# 17_-ETH_CONNECTOR.net
KiCad netlist of a schematic drawn in Altium Designer
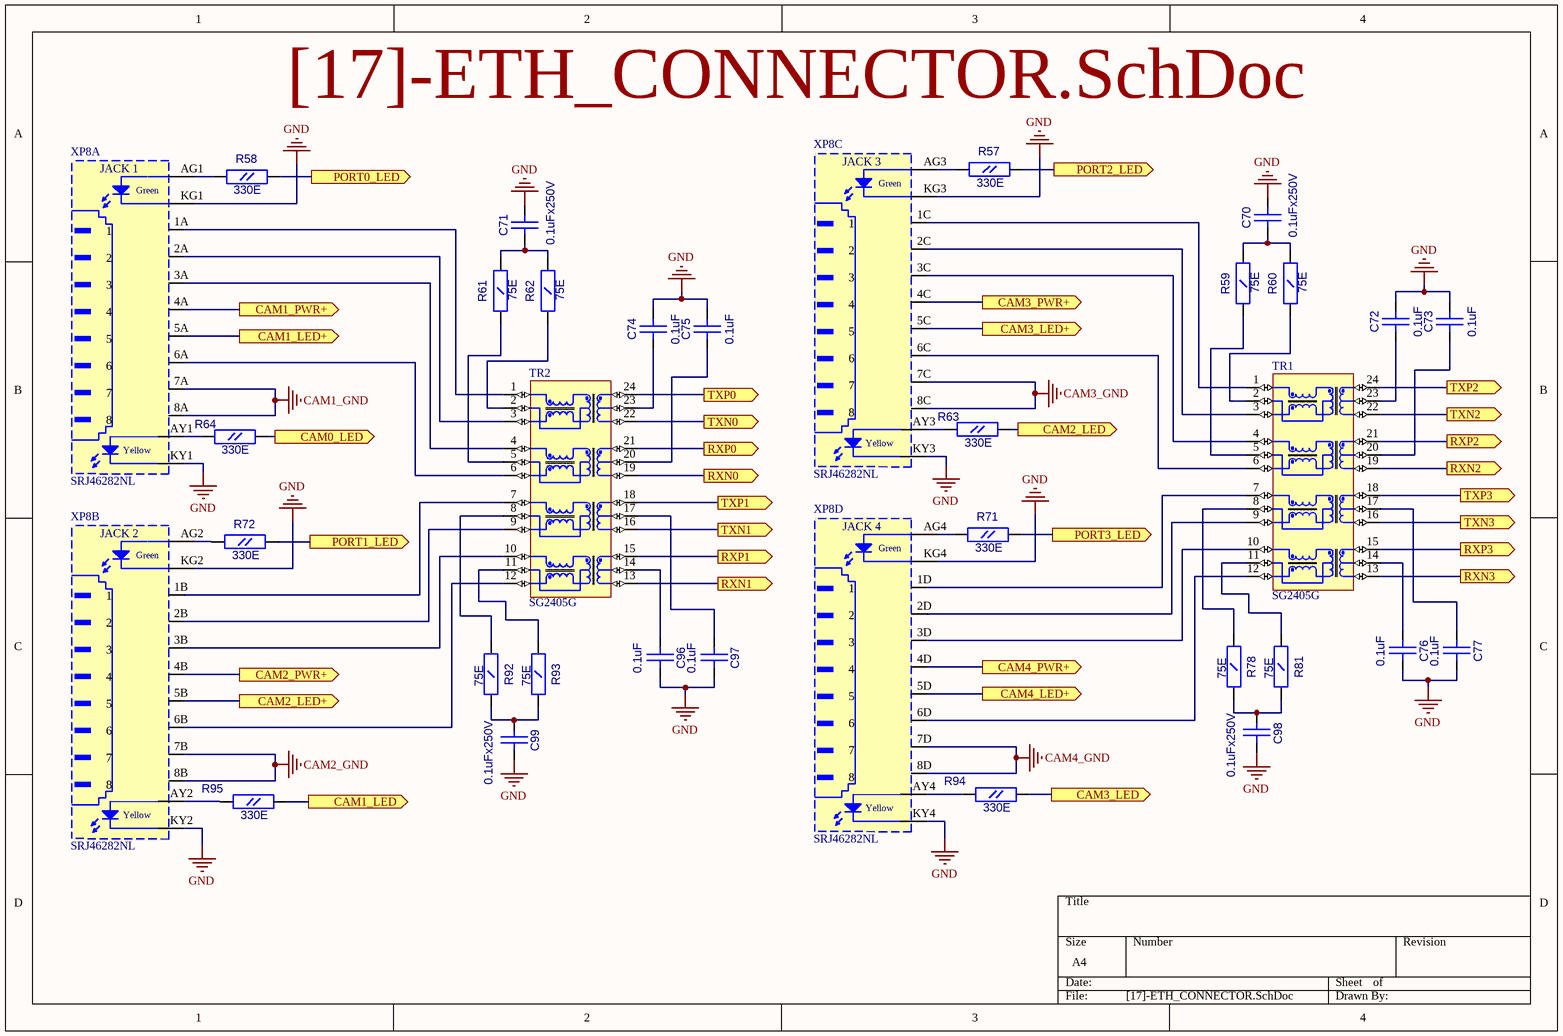
[diagram p0: [17]-ETH_CONNECTOR.SchDoc]

(export (version "E")
  (design (tool "Eeschema 10.0.6"))
  (components
    (comp (ref "C70")
      (value "0.1uFx250V")
      (footprint "CC1206")
      (description "CC1206")
      (libsource (lib "fizik_lib (1)") (part "CC1206"))
    )
    (comp (ref "C71")
      (value "0.1uFx250V")
      (footprint "CC1206")
      (description "CC1206")
      (libsource (lib "fizik_lib (1)") (part "CC1206"))
    )
    (comp (ref "C72")
      (value "0.1uF")
      (footprint "CC0603")
      (description "CC0603")
      (libsource (lib "fizik_lib") (part "CC0603"))
    )
    (comp (ref "C73")
      (value "0.1uF")
      (footprint "CC0603")
      (description "CC0603")
      (libsource (lib "fizik_lib") (part "CC0603"))
    )
    (comp (ref "C74")
      (value "0.1uF")
      (footprint "CC0603")
      (description "CC0603")
      (libsource (lib "fizik_lib") (part "CC0603"))
    )
    (comp (ref "C75")
      (value "0.1uF")
      (footprint "CC0603")
      (description "CC0603")
      (libsource (lib "fizik_lib") (part "CC0603"))
    )
    (comp (ref "C76")
      (value "0.1uF")
      (footprint "CC0603")
      (description "CC0603")
      (libsource (lib "fizik_lib") (part "CC0603"))
    )
    (comp (ref "C77")
      (value "0.1uF")
      (footprint "CC0603")
      (description "CC0603")
      (libsource (lib "fizik_lib") (part "CC0603"))
    )
    (comp (ref "C96")
      (value "0.1uF")
      (footprint "CC0603")
      (description "CC0603")
      (libsource (lib "fizik_lib") (part "CC0603"))
    )
    (comp (ref "C97")
      (value "0.1uF")
      (footprint "CC0603")
      (description "CC0603")
      (libsource (lib "fizik_lib") (part "CC0603"))
    )
    (comp (ref "C98")
      (value "0.1uFx250V")
      (footprint "CC1206")
      (description "CC1206")
      (libsource (lib "fizik_lib (1)") (part "CC1206"))
    )
    (comp (ref "C99")
      (value "0.1uFx250V")
      (footprint "CC1206")
      (description "CC1206")
      (libsource (lib "fizik_lib (1)") (part "CC1206"))
    )
    (comp (ref "R57")
      (value "330E")
      (footprint "RC0603")
      (description "RC0603")
      (libsource (lib "fizik_lib") (part "RC0603"))
    )
    (comp (ref "R58")
      (value "330E")
      (footprint "RC0603")
      (description "RC0603")
      (libsource (lib "fizik_lib") (part "RC0603"))
    )
    (comp (ref "R59")
      (value "75E")
      (footprint "RC1206")
      (description "RC1206")
      (libsource (lib "fizik_lib (1)") (part "RC1206"))
    )
    (comp (ref "R60")
      (value "75E")
      (footprint "RC1206")
      (description "RC1206")
      (libsource (lib "fizik_lib (1)") (part "RC1206"))
    )
    (comp (ref "R61")
      (value "75E")
      (footprint "RC1206")
      (description "RC1206")
      (libsource (lib "fizik_lib (1)") (part "RC1206"))
    )
    (comp (ref "R62")
      (value "75E")
      (footprint "RC1206")
      (description "RC1206")
      (libsource (lib "fizik_lib (1)") (part "RC1206"))
    )
    (comp (ref "R63")
      (value "330E")
      (footprint "RC0603")
      (description "RC0603")
      (libsource (lib "fizik_lib") (part "RC0603"))
    )
    (comp (ref "R64")
      (value "330E")
      (footprint "RC0603")
      (description "RC0603")
      (libsource (lib "fizik_lib") (part "RC0603"))
    )
    (comp (ref "R71")
      (value "330E")
      (footprint "RC0603")
      (description "RC0603")
      (libsource (lib "fizik_lib") (part "RC0603"))
    )
    (comp (ref "R72")
      (value "330E")
      (footprint "RC0603")
      (description "RC0603")
      (libsource (lib "fizik_lib") (part "RC0603"))
    )
    (comp (ref "R78")
      (value "75E")
      (footprint "RC1206")
      (description "RC1206")
      (libsource (lib "fizik_lib (1)") (part "RC1206"))
    )
    (comp (ref "R81")
      (value "75E")
      (footprint "RC1206")
      (description "RC1206")
      (libsource (lib "fizik_lib (1)") (part "RC1206"))
    )
    (comp (ref "R92")
      (value "75E")
      (footprint "RC1206")
      (description "RC1206")
      (libsource (lib "fizik_lib (1)") (part "RC1206"))
    )
    (comp (ref "R93")
      (value "75E")
      (footprint "RC1206")
      (description "RC1206")
      (libsource (lib "fizik_lib (1)") (part "RC1206"))
    )
    (comp (ref "R94")
      (value "330E")
      (footprint "RC0603")
      (description "RC0603")
      (libsource (lib "fizik_lib") (part "RC0603"))
    )
    (comp (ref "R95")
      (value "330E")
      (footprint "RC0603")
      (description "RC0603")
      (libsource (lib "fizik_lib") (part "RC0603"))
    )
    (comp (ref "TR1")
      (value "SG2405G")
      (footprint "SG2405G")
      (description "Ehternet transformer Gigabit or 2 LAN10/100")
      (libsource (lib "fizik_lib (1)") (part "SG2405G"))
    )
    (comp (ref "TR2")
      (value "SG2405G")
      (footprint "SG2405G")
      (description "Ehternet transformer Gigabit or 2 LAN10/100")
      (libsource (lib "fizik_lib (1)") (part "SG2405G"))
    )
    (comp (ref "XP8")
      (value "SRJ46282NL")
      (footprint "SRJ46282NL")
      (libsource (lib "fizik_lib (1)") (part "SRJ46282NL"))
    )
  )
  (nets
    (net (code "1") (name "/CAM0_LED") (class "Default")
      (node (ref "R64") (pin "2") (pinfunction "B_2") (pintype "passive"))
    )
    (net (code "2") (name "/CAM1_LED") (class "Default")
      (node (ref "R95") (pin "2") (pinfunction "B_2") (pintype "passive"))
    )
    (net (code "3") (name "/CAM1_LED+") (class "Default")
      (node (ref "XP8") (pin "5A") (pinfunction "1_5A") (pintype "passive"))
    )
    (net (code "4") (name "/CAM1_PWR+") (class "Default")
      (node (ref "XP8") (pin "4A") (pinfunction "1_4A") (pintype "passive"))
    )
    (net (code "5") (name "/CAM2_LED") (class "Default")
      (node (ref "R63") (pin "2") (pinfunction "B_2") (pintype "passive"))
    )
    (net (code "6") (name "/CAM2_LED+") (class "Default")
      (node (ref "XP8") (pin "5B") (pinfunction "1_5B") (pintype "passive"))
    )
    (net (code "7") (name "/CAM2_PWR+") (class "Default")
      (node (ref "XP8") (pin "4B") (pinfunction "1_4B") (pintype "passive"))
    )
    (net (code "8") (name "/CAM3_LED") (class "Default")
      (node (ref "R94") (pin "2") (pinfunction "B_2") (pintype "passive"))
    )
    (net (code "9") (name "/CAM3_LED+") (class "Default")
      (node (ref "XP8") (pin "5C") (pinfunction "1_5C") (pintype "passive"))
    )
    (net (code "10") (name "/CAM3_PWR+") (class "Default")
      (node (ref "XP8") (pin "4C") (pinfunction "1_4C") (pintype "passive"))
    )
    (net (code "11") (name "/CAM4_LED+") (class "Default")
      (node (ref "XP8") (pin "5D") (pinfunction "1_5D") (pintype "passive"))
    )
    (net (code "12") (name "/CAM4_PWR+") (class "Default")
      (node (ref "XP8") (pin "4D") (pinfunction "1_4D") (pintype "passive"))
    )
    (net (code "13") (name "/PORT0_LED") (class "Default")
      (node (ref "R58") (pin "2") (pinfunction "B_2") (pintype "passive"))
    )
    (net (code "14") (name "/PORT1_LED") (class "Default")
      (node (ref "R72") (pin "2") (pinfunction "B_2") (pintype "passive"))
    )
    (net (code "15") (name "/PORT2_LED") (class "Default")
      (node (ref "R57") (pin "2") (pinfunction "B_2") (pintype "passive"))
    )
    (net (code "16") (name "/PORT3_LED") (class "Default")
      (node (ref "R71") (pin "2") (pinfunction "B_2") (pintype "passive"))
    )
    (net (code "17") (name "/RXN0") (class "Default")
      (node (ref "TR2") (pin "19") (pinfunction "TX1-_19") (pintype "bidirectional"))
    )
    (net (code "18") (name "/RXN1") (class "Default")
      (node (ref "TR2") (pin "13") (pinfunction "RX2-_13") (pintype "bidirectional"))
    )
    (net (code "19") (name "/RXN2") (class "Default")
      (node (ref "TR1") (pin "19") (pinfunction "TX1-_19") (pintype "bidirectional"))
    )
    (net (code "20") (name "/RXN3") (class "Default")
      (node (ref "TR1") (pin "13") (pinfunction "RX2-_13") (pintype "bidirectional"))
    )
    (net (code "21") (name "/RXP0") (class "Default")
      (node (ref "TR2") (pin "21") (pinfunction "TX1+_21") (pintype "bidirectional"))
    )
    (net (code "22") (name "/RXP1") (class "Default")
      (node (ref "TR2") (pin "15") (pinfunction "RX2+_15") (pintype "bidirectional"))
    )
    (net (code "23") (name "/RXP2") (class "Default")
      (node (ref "TR1") (pin "21") (pinfunction "TX1+_21") (pintype "bidirectional"))
    )
    (net (code "24") (name "/RXP3") (class "Default")
      (node (ref "TR1") (pin "15") (pinfunction "RX2+_15") (pintype "bidirectional"))
    )
    (net (code "25") (name "/TXN0") (class "Default")
      (node (ref "TR2") (pin "22") (pinfunction "RX1-_22") (pintype "bidirectional"))
    )
    (net (code "26") (name "/TXN1") (class "Default")
      (node (ref "TR2") (pin "16") (pinfunction "TX2-_16") (pintype "bidirectional"))
    )
    (net (code "27") (name "/TXN2") (class "Default")
      (node (ref "TR1") (pin "22") (pinfunction "RX1-_22") (pintype "bidirectional"))
    )
    (net (code "28") (name "/TXN3") (class "Default")
      (node (ref "TR1") (pin "16") (pinfunction "TX2-_16") (pintype "bidirectional"))
    )
    (net (code "29") (name "/TXP0") (class "Default")
      (node (ref "TR2") (pin "24") (pinfunction "RX1+_24") (pintype "bidirectional"))
    )
    (net (code "30") (name "/TXP1") (class "Default")
      (node (ref "TR2") (pin "18") (pinfunction "TX2+_18") (pintype "bidirectional"))
    )
    (net (code "31") (name "/TXP2") (class "Default")
      (node (ref "TR1") (pin "24") (pinfunction "RX1+_24") (pintype "bidirectional"))
    )
    (net (code "32") (name "/TXP3") (class "Default")
      (node (ref "TR1") (pin "18") (pinfunction "TX2+_18") (pintype "bidirectional"))
    )
    (net (code "33") (name "CAM1_GND") (class "Default")
      (node (ref "XP8") (pin "7A") (pinfunction "1_7A") (pintype "passive"))
      (node (ref "XP8") (pin "8A") (pinfunction "1_8A") (pintype "passive"))
    )
    (net (code "34") (name "CAM2_GND") (class "Default")
      (node (ref "XP8") (pin "7B") (pinfunction "1_7B") (pintype "passive"))
      (node (ref "XP8") (pin "8B") (pinfunction "1_8B") (pintype "passive"))
    )
    (net (code "35") (name "CAM3_GND") (class "Default")
      (node (ref "XP8") (pin "7C") (pinfunction "1_7C") (pintype "passive"))
      (node (ref "XP8") (pin "8C") (pinfunction "1_8C") (pintype "passive"))
    )
    (net (code "36") (name "CAM4_GND") (class "Default")
      (node (ref "XP8") (pin "7D") (pinfunction "1_7D") (pintype "passive"))
      (node (ref "XP8") (pin "8D") (pinfunction "1_8D") (pintype "passive"))
    )
    (net (code "37") (name "GND") (class "Default")
      (node (ref "C70") (pin "2") (pinfunction "B_2") (pintype "passive"))
      (node (ref "C71") (pin "2") (pinfunction "B_2") (pintype "passive"))
      (node (ref "C72") (pin "2") (pinfunction "B_2") (pintype "passive"))
      (node (ref "C73") (pin "2") (pinfunction "B_2") (pintype "passive"))
      (node (ref "C74") (pin "2") (pinfunction "B_2") (pintype "passive"))
      (node (ref "C75") (pin "2") (pinfunction "B_2") (pintype "passive"))
      (node (ref "C76") (pin "2") (pinfunction "B_2") (pintype "passive"))
      (node (ref "C77") (pin "2") (pinfunction "B_2") (pintype "passive"))
      (node (ref "C96") (pin "2") (pinfunction "B_2") (pintype "passive"))
      (node (ref "C97") (pin "2") (pinfunction "B_2") (pintype "passive"))
      (node (ref "C98") (pin "2") (pinfunction "B_2") (pintype "passive"))
      (node (ref "C99") (pin "2") (pinfunction "B_2") (pintype "passive"))
      (node (ref "XP8") (pin "KG1") (pinfunction "D2_KG1") (pintype "passive"))
      (node (ref "XP8") (pin "KG2") (pinfunction "D2_KG2") (pintype "passive"))
      (node (ref "XP8") (pin "KG3") (pinfunction "D2_KG3") (pintype "passive"))
      (node (ref "XP8") (pin "KG4") (pinfunction "D2_KG4") (pintype "passive"))
      (node (ref "XP8") (pin "KY1") (pinfunction "D4_KY1") (pintype "passive"))
      (node (ref "XP8") (pin "KY2") (pinfunction "D4_KY2") (pintype "passive"))
      (node (ref "XP8") (pin "KY3") (pinfunction "D4_KY3") (pintype "passive"))
      (node (ref "XP8") (pin "KY4") (pinfunction "D4_KY4") (pintype "passive"))
    )
    (net (code "38") (name "Net-(C70-A)") (class "Default")
      (node (ref "C70") (pin "1") (pinfunction "A_1") (pintype "passive"))
      (node (ref "R59") (pin "2") (pinfunction "B_2") (pintype "passive"))
      (node (ref "R60") (pin "2") (pinfunction "B_2") (pintype "passive"))
    )
    (net (code "39") (name "Net-(C71-A)") (class "Default")
      (node (ref "C71") (pin "1") (pinfunction "A_1") (pintype "passive"))
      (node (ref "R61") (pin "2") (pinfunction "B_2") (pintype "passive"))
      (node (ref "R62") (pin "2") (pinfunction "B_2") (pintype "passive"))
    )
    (net (code "40") (name "Net-(C72-A)") (class "Default")
      (node (ref "C72") (pin "1") (pinfunction "A_1") (pintype "passive"))
      (node (ref "TR1") (pin "23") (pinfunction "RXCT1_23") (pintype "bidirectional"))
    )
    (net (code "41") (name "Net-(C73-A)") (class "Default")
      (node (ref "C73") (pin "1") (pinfunction "A_1") (pintype "passive"))
      (node (ref "TR1") (pin "20") (pinfunction "TXCT1_20") (pintype "bidirectional"))
    )
    (net (code "42") (name "Net-(C74-A)") (class "Default")
      (node (ref "C74") (pin "1") (pinfunction "A_1") (pintype "passive"))
      (node (ref "TR2") (pin "23") (pinfunction "RXCT1_23") (pintype "bidirectional"))
    )
    (net (code "43") (name "Net-(C75-A)") (class "Default")
      (node (ref "C75") (pin "1") (pinfunction "A_1") (pintype "passive"))
      (node (ref "TR2") (pin "20") (pinfunction "TXCT1_20") (pintype "bidirectional"))
    )
    (net (code "44") (name "Net-(C76-A)") (class "Default")
      (node (ref "C76") (pin "1") (pinfunction "A_1") (pintype "passive"))
      (node (ref "TR1") (pin "14") (pinfunction "RXCT2_14") (pintype "bidirectional"))
    )
    (net (code "45") (name "Net-(C77-A)") (class "Default")
      (node (ref "C77") (pin "1") (pinfunction "A_1") (pintype "passive"))
      (node (ref "TR1") (pin "17") (pinfunction "TXCT2_17") (pintype "bidirectional"))
    )
    (net (code "46") (name "Net-(C96-A)") (class "Default")
      (node (ref "C96") (pin "1") (pinfunction "A_1") (pintype "passive"))
      (node (ref "TR2") (pin "14") (pinfunction "RXCT2_14") (pintype "bidirectional"))
    )
    (net (code "47") (name "Net-(C97-A)") (class "Default")
      (node (ref "C97") (pin "1") (pinfunction "A_1") (pintype "passive"))
      (node (ref "TR2") (pin "17") (pinfunction "TXCT2_17") (pintype "bidirectional"))
    )
    (net (code "48") (name "Net-(C98-A)") (class "Default")
      (node (ref "C98") (pin "1") (pinfunction "A_1") (pintype "passive"))
      (node (ref "R78") (pin "2") (pinfunction "B_2") (pintype "passive"))
      (node (ref "R81") (pin "2") (pinfunction "B_2") (pintype "passive"))
    )
    (net (code "49") (name "Net-(C99-A)") (class "Default")
      (node (ref "C99") (pin "1") (pinfunction "A_1") (pintype "passive"))
      (node (ref "R92") (pin "2") (pinfunction "B_2") (pintype "passive"))
      (node (ref "R93") (pin "2") (pinfunction "B_2") (pintype "passive"))
    )
    (net (code "50") (name "Net-(R57-A)") (class "Default")
      (node (ref "R57") (pin "1") (pinfunction "A_1") (pintype "passive"))
      (node (ref "XP8") (pin "AG3") (pinfunction "D1_AG3") (pintype "passive"))
    )
    (net (code "51") (name "Net-(R58-A)") (class "Default")
      (node (ref "R58") (pin "1") (pinfunction "A_1") (pintype "passive"))
      (node (ref "XP8") (pin "AG1") (pinfunction "D1_AG1") (pintype "passive"))
    )
    (net (code "52") (name "Net-(R59-A)") (class "Default")
      (node (ref "R59") (pin "1") (pinfunction "A_1") (pintype "passive"))
      (node (ref "TR1") (pin "5") (pinfunction "TCT1_5") (pintype "bidirectional"))
    )
    (net (code "53") (name "Net-(R60-A)") (class "Default")
      (node (ref "R60") (pin "1") (pinfunction "A_1") (pintype "passive"))
      (node (ref "TR1") (pin "2") (pinfunction "RCT1_2") (pintype "bidirectional"))
    )
    (net (code "54") (name "Net-(R61-A)") (class "Default")
      (node (ref "R61") (pin "1") (pinfunction "A_1") (pintype "passive"))
      (node (ref "TR2") (pin "5") (pinfunction "TCT1_5") (pintype "bidirectional"))
    )
    (net (code "55") (name "Net-(R62-A)") (class "Default")
      (node (ref "R62") (pin "1") (pinfunction "A_1") (pintype "passive"))
      (node (ref "TR2") (pin "2") (pinfunction "RCT1_2") (pintype "bidirectional"))
    )
    (net (code "56") (name "Net-(R63-A)") (class "Default")
      (node (ref "R63") (pin "1") (pinfunction "A_1") (pintype "passive"))
      (node (ref "XP8") (pin "AY3") (pinfunction "D3_AY3") (pintype "passive"))
    )
    (net (code "57") (name "Net-(R64-A)") (class "Default")
      (node (ref "R64") (pin "1") (pinfunction "A_1") (pintype "passive"))
      (node (ref "XP8") (pin "AY1") (pinfunction "D3_AY1") (pintype "passive"))
    )
    (net (code "58") (name "Net-(R71-A)") (class "Default")
      (node (ref "R71") (pin "1") (pinfunction "A_1") (pintype "passive"))
      (node (ref "XP8") (pin "AG4") (pinfunction "D1_AG4") (pintype "passive"))
    )
    (net (code "59") (name "Net-(R72-A)") (class "Default")
      (node (ref "R72") (pin "1") (pinfunction "A_1") (pintype "passive"))
      (node (ref "XP8") (pin "AG2") (pinfunction "D1_AG2") (pintype "passive"))
    )
    (net (code "60") (name "Net-(R78-A)") (class "Default")
      (node (ref "R78") (pin "1") (pinfunction "A_1") (pintype "passive"))
      (node (ref "TR1") (pin "8") (pinfunction "TCT2_8") (pintype "bidirectional"))
    )
    (net (code "61") (name "Net-(R81-A)") (class "Default")
      (node (ref "R81") (pin "1") (pinfunction "A_1") (pintype "passive"))
      (node (ref "TR1") (pin "11") (pinfunction "RCT2_11") (pintype "bidirectional"))
    )
    (net (code "62") (name "Net-(R92-A)") (class "Default")
      (node (ref "R92") (pin "1") (pinfunction "A_1") (pintype "passive"))
      (node (ref "TR2") (pin "8") (pinfunction "TCT2_8") (pintype "bidirectional"))
    )
    (net (code "63") (name "Net-(R93-A)") (class "Default")
      (node (ref "R93") (pin "1") (pinfunction "A_1") (pintype "passive"))
      (node (ref "TR2") (pin "11") (pinfunction "RCT2_11") (pintype "bidirectional"))
    )
    (net (code "64") (name "Net-(R94-A)") (class "Default")
      (node (ref "R94") (pin "1") (pinfunction "A_1") (pintype "passive"))
      (node (ref "XP8") (pin "AY4") (pinfunction "D3_AY4") (pintype "passive"))
    )
    (net (code "65") (name "Net-(R95-A)") (class "Default")
      (node (ref "R95") (pin "1") (pinfunction "A_1") (pintype "passive"))
      (node (ref "XP8") (pin "AY2") (pinfunction "D3_AY2") (pintype "passive"))
    )
    (net (code "66") (name "Net-(TR1-RD1+)") (class "Default")
      (node (ref "TR1") (pin "1") (pinfunction "RD1+_1") (pintype "bidirectional"))
      (node (ref "XP8") (pin "1C") (pinfunction "1_1C") (pintype "passive"))
    )
    (net (code "67") (name "Net-(TR1-RD1-)") (class "Default")
      (node (ref "TR1") (pin "3") (pinfunction "RD1-_3") (pintype "bidirectional"))
      (node (ref "XP8") (pin "2C") (pinfunction "1_2C") (pintype "passive"))
    )
    (net (code "68") (name "Net-(TR1-RD2+)") (class "Default")
      (node (ref "TR1") (pin "10") (pinfunction "RD2+_10") (pintype "bidirectional"))
      (node (ref "XP8") (pin "3D") (pinfunction "1_3D") (pintype "passive"))
    )
    (net (code "69") (name "Net-(TR1-RD2-)") (class "Default")
      (node (ref "TR1") (pin "12") (pinfunction "RD2-_12") (pintype "bidirectional"))
      (node (ref "XP8") (pin "6D") (pinfunction "1_6D") (pintype "passive"))
    )
    (net (code "70") (name "Net-(TR1-TD1+)") (class "Default")
      (node (ref "TR1") (pin "4") (pinfunction "TD1+_4") (pintype "bidirectional"))
      (node (ref "XP8") (pin "3C") (pinfunction "1_3C") (pintype "passive"))
    )
    (net (code "71") (name "Net-(TR1-TD1-)") (class "Default")
      (node (ref "TR1") (pin "6") (pinfunction "TD1-_6") (pintype "bidirectional"))
      (node (ref "XP8") (pin "6C") (pinfunction "1_6C") (pintype "passive"))
    )
    (net (code "72") (name "Net-(TR1-TD2+)") (class "Default")
      (node (ref "TR1") (pin "7") (pinfunction "TD2+_7") (pintype "bidirectional"))
      (node (ref "XP8") (pin "1D") (pinfunction "1_1D") (pintype "passive"))
    )
    (net (code "73") (name "Net-(TR1-TD2-)") (class "Default")
      (node (ref "TR1") (pin "9") (pinfunction "TD2-_9") (pintype "bidirectional"))
      (node (ref "XP8") (pin "2D") (pinfunction "1_2D") (pintype "passive"))
    )
    (net (code "74") (name "Net-(TR2-RD1+)") (class "Default")
      (node (ref "TR2") (pin "1") (pinfunction "RD1+_1") (pintype "bidirectional"))
      (node (ref "XP8") (pin "1A") (pinfunction "1_1A") (pintype "passive"))
    )
    (net (code "75") (name "Net-(TR2-RD1-)") (class "Default")
      (node (ref "TR2") (pin "3") (pinfunction "RD1-_3") (pintype "bidirectional"))
      (node (ref "XP8") (pin "2A") (pinfunction "1_2A") (pintype "passive"))
    )
    (net (code "76") (name "Net-(TR2-RD2+)") (class "Default")
      (node (ref "TR2") (pin "10") (pinfunction "RD2+_10") (pintype "bidirectional"))
      (node (ref "XP8") (pin "3B") (pinfunction "1_3B") (pintype "passive"))
    )
    (net (code "77") (name "Net-(TR2-RD2-)") (class "Default")
      (node (ref "TR2") (pin "12") (pinfunction "RD2-_12") (pintype "bidirectional"))
      (node (ref "XP8") (pin "6B") (pinfunction "1_6B") (pintype "passive"))
    )
    (net (code "78") (name "Net-(TR2-TD1+)") (class "Default")
      (node (ref "TR2") (pin "4") (pinfunction "TD1+_4") (pintype "bidirectional"))
      (node (ref "XP8") (pin "3A") (pinfunction "1_3A") (pintype "passive"))
    )
    (net (code "79") (name "Net-(TR2-TD1-)") (class "Default")
      (node (ref "TR2") (pin "6") (pinfunction "TD1-_6") (pintype "bidirectional"))
      (node (ref "XP8") (pin "6A") (pinfunction "1_6A") (pintype "passive"))
    )
    (net (code "80") (name "Net-(TR2-TD2+)") (class "Default")
      (node (ref "TR2") (pin "7") (pinfunction "TD2+_7") (pintype "bidirectional"))
      (node (ref "XP8") (pin "1B") (pinfunction "1_1B") (pintype "passive"))
    )
    (net (code "81") (name "Net-(TR2-TD2-)") (class "Default")
      (node (ref "TR2") (pin "9") (pinfunction "TD2-_9") (pintype "bidirectional"))
      (node (ref "XP8") (pin "2B") (pinfunction "1_2B") (pintype "passive"))
    )
  )
)
